# FRDM-TFC.net
KiCad netlist of a schematic drawn in Altium Designer
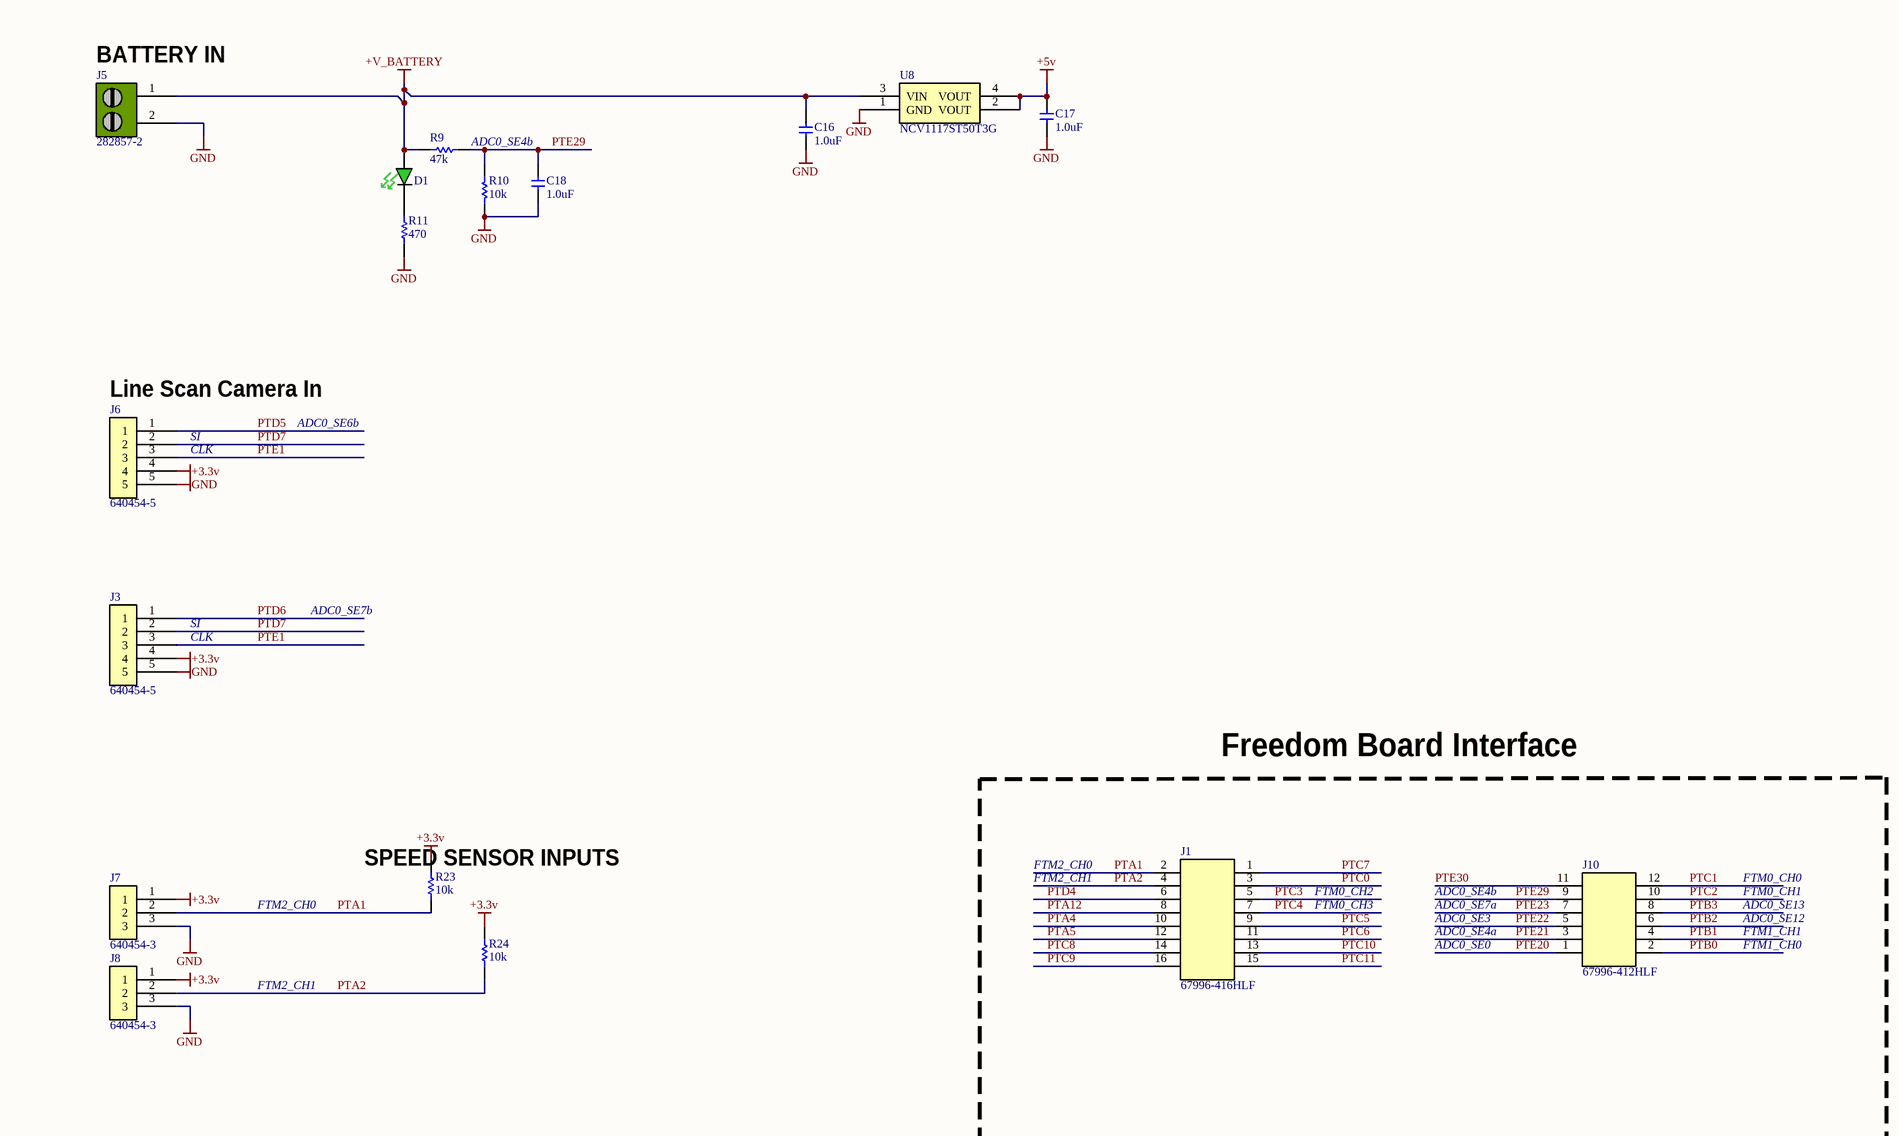
[diagram p0: FRDM-TFC.SchDoc, top left]
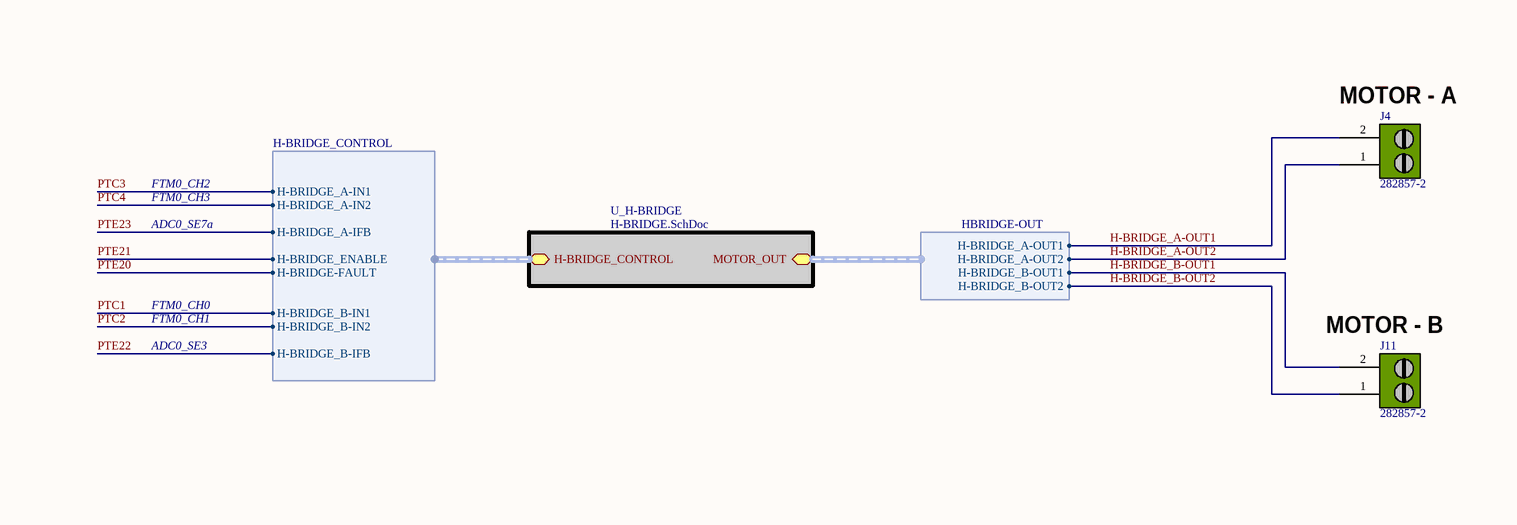
[diagram p1: FRDM-TFC.SchDoc, top right]
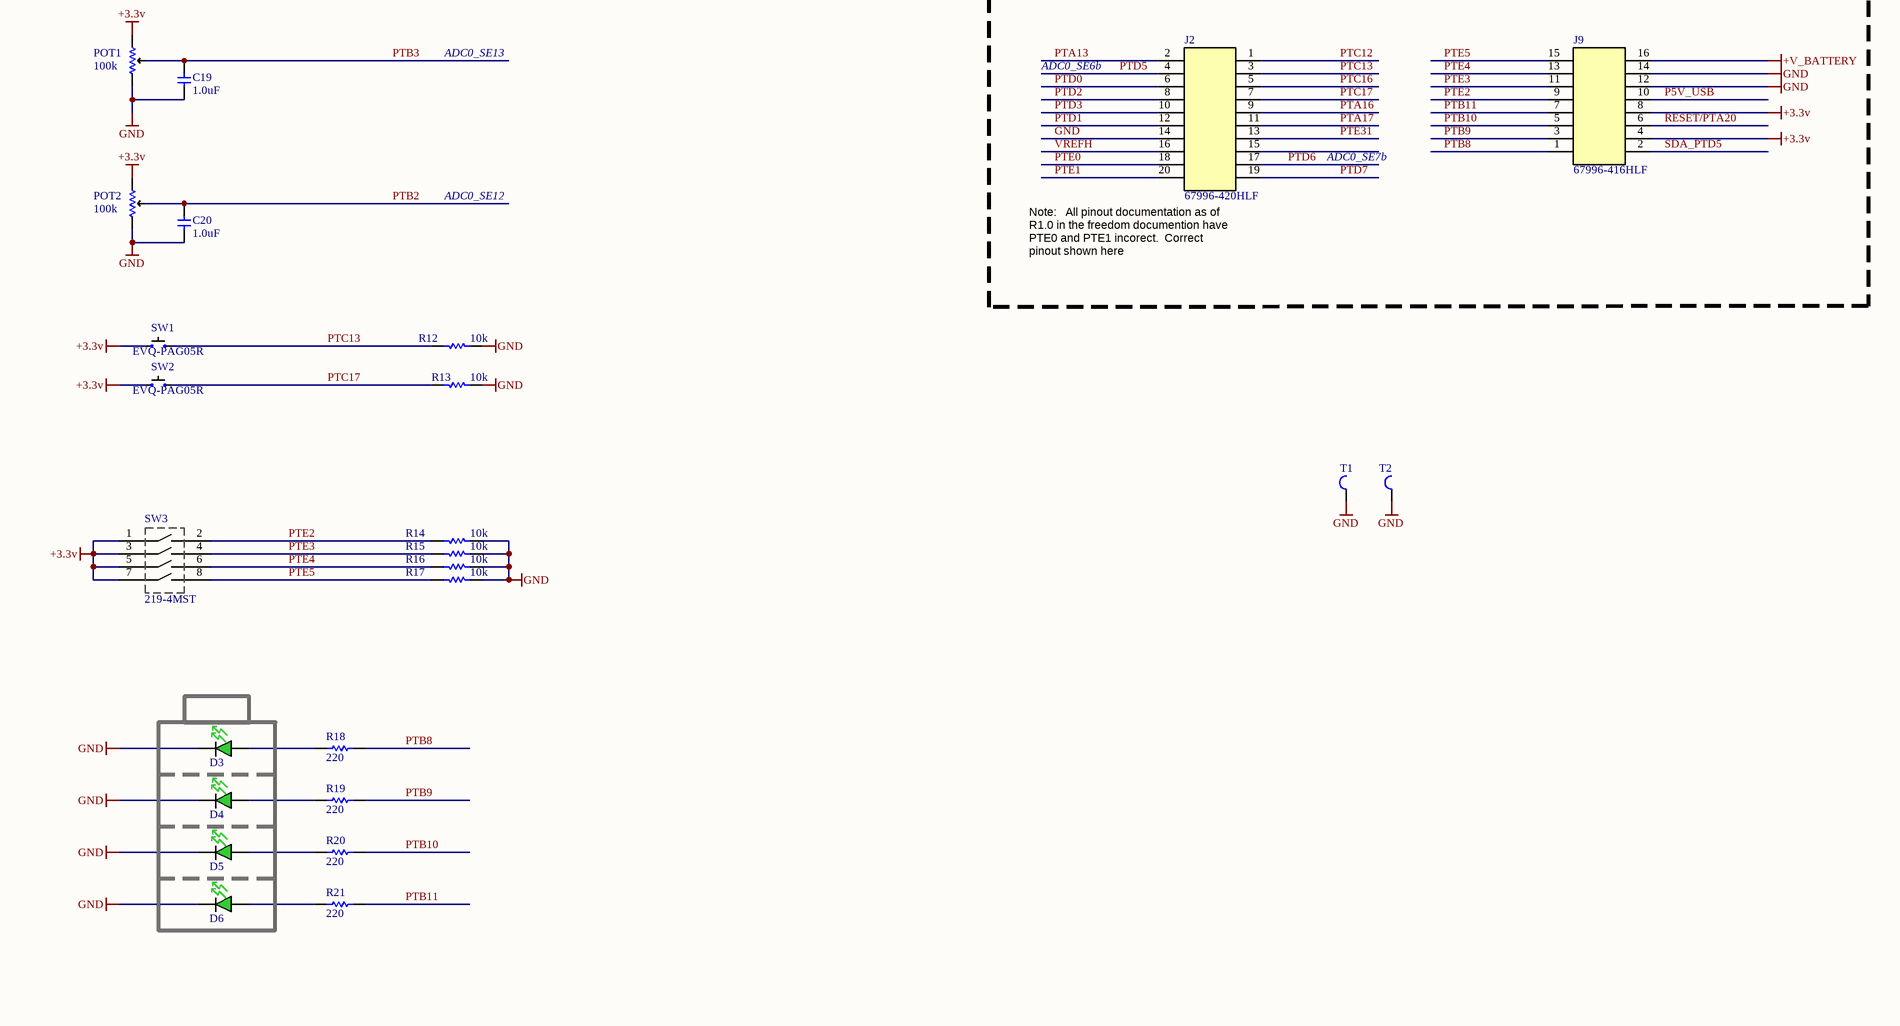
[diagram p2: FRDM-TFC.SchDoc, bottom left]
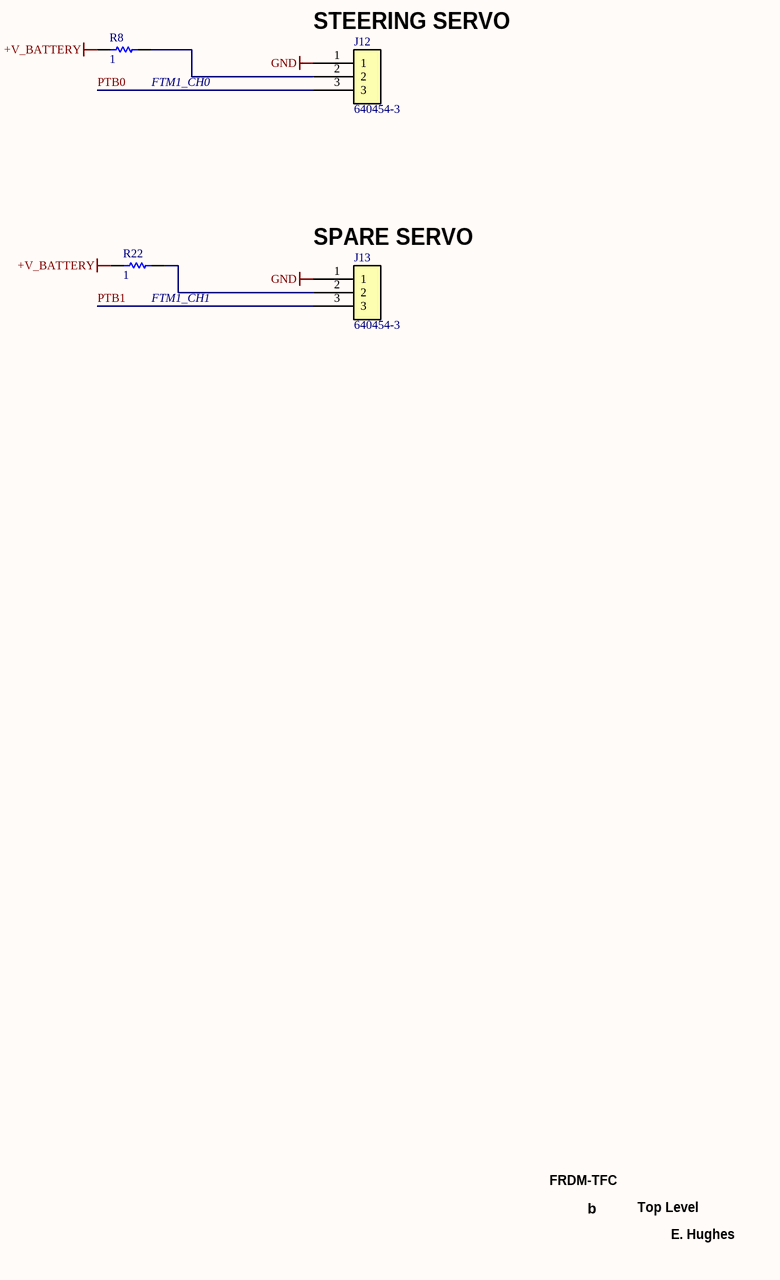
[diagram p3: FRDM-TFC.SchDoc, bottom right]

(export (version "E")
  (design (tool "Eeschema 10.0.6"))
  (components
    (comp (ref "C16")
      (value "1.0uF")
      (footprint "C0805")
      (description "CAP CER 1.0UF 50V X5R 0805")
      (fields
        (field (name "MANUFACTURER") "Taiyo Yuden")
        (field (name "MANUFACTURER PART NUMBER") "UMK212BJ105KG-T")
      )
      (libsource (lib "eCapacitors") (part "UMK212BJ105KG-T"))
    )
    (comp (ref "C17")
      (value "1.0uF")
      (footprint "C0805")
      (description "CAP CER 1.0UF 50V X5R 0805")
      (fields
        (field (name "MANUFACTURER") "Taiyo Yuden")
        (field (name "MANUFACTURER PART NUMBER") "UMK212BJ105KG-T")
      )
      (libsource (lib "eCapacitors") (part "UMK212BJ105KG-T"))
    )
    (comp (ref "C18")
      (value "1.0uF")
      (footprint "C0805")
      (description "CAP CER 1.0UF 50V X5R 0805")
      (fields
        (field (name "MANUFACTURER") "Taiyo Yuden")
        (field (name "MANUFACTURER PART NUMBER") "UMK212BJ105KG-T")
      )
      (libsource (lib "eCapacitors") (part "UMK212BJ105KG-T"))
    )
    (comp (ref "C19")
      (value "1.0uF")
      (footprint "C0805")
      (description "CAP CER 1.0UF 50V X5R 0805")
      (fields
        (field (name "MANUFACTURER") "Taiyo Yuden")
        (field (name "MANUFACTURER PART NUMBER") "UMK212BJ105KG-T")
      )
      (libsource (lib "eCapacitors") (part "UMK212BJ105KG-T"))
    )
    (comp (ref "C20")
      (value "1.0uF")
      (footprint "C0805")
      (description "CAP CER 1.0UF 50V X5R 0805")
      (fields
        (field (name "MANUFACTURER") "Taiyo Yuden")
        (field (name "MANUFACTURER PART NUMBER") "UMK212BJ105KG-T")
      )
      (libsource (lib "eCapacitors") (part "UMK212BJ105KG-T"))
    )
    (comp (ref "D1")
      (value "~")
      (footprint "LED_0805 - GREEN")
      (description "LED 2X1.2MM 570NM GN WTR CLR SMD")
      (fields
        (field (name "MANUFACTURER") "Kingbright Corp")
        (field (name "MANUFACTURER PART NUMBER") "APT2012CGCK")
      )
      (libsource (lib "eDiode") (part "APT2012CGCK"))
    )
    (comp (ref "D3")
      (value "~")
      (footprint "LED_0805 - GREEN")
      (description "LED 2X1.2MM 570NM GN WTR CLR SMD")
      (fields
        (field (name "MANUFACTURER") "Kingbright Corp")
        (field (name "MANUFACTURER PART NUMBER") "APT2012CGCK")
      )
      (libsource (lib "eDiode") (part "APT2012CGCK"))
    )
    (comp (ref "D4")
      (value "~")
      (footprint "LED_0805 - GREEN")
      (description "LED 2X1.2MM 570NM GN WTR CLR SMD")
      (fields
        (field (name "MANUFACTURER") "Kingbright Corp")
        (field (name "MANUFACTURER PART NUMBER") "APT2012CGCK")
      )
      (libsource (lib "eDiode") (part "APT2012CGCK"))
    )
    (comp (ref "D5")
      (value "~")
      (footprint "LED_0805 - GREEN")
      (description "LED 2X1.2MM 570NM GN WTR CLR SMD")
      (fields
        (field (name "MANUFACTURER") "Kingbright Corp")
        (field (name "MANUFACTURER PART NUMBER") "APT2012CGCK")
      )
      (libsource (lib "eDiode") (part "APT2012CGCK"))
    )
    (comp (ref "D6")
      (value "~")
      (footprint "LED_0805 - GREEN")
      (description "LED 2X1.2MM 570NM GN WTR CLR SMD")
      (fields
        (field (name "MANUFACTURER") "Kingbright Corp")
        (field (name "MANUFACTURER PART NUMBER") "APT2012CGCK")
      )
      (libsource (lib "eDiode") (part "APT2012CGCK"))
    )
    (comp (ref "J1")
      (value "67996-416HLF")
      (footprint "67996-416HLF")
      (description "CONN HEADER 16POS .100 STR TIN")
      (fields (field (name "MANUFACTURER") "FCI"))
      (libsource (lib "") (part "67996-416HLF_1"))
    )
    (comp (ref "J2")
      (value "67996-420HLF")
      (footprint "67996-420HLF")
      (description "CONN HEADER 20POS .100 STR TIN")
      (fields (field (name "MANUFACTURER") "FCI"))
      (libsource (lib "eConnector") (part "67996-420HLF"))
    )
    (comp (ref "J3")
      (value "640454-5")
      (footprint "640454-5")
      (description "CONN HEADER VERT 5POS .100 TIN")
      (fields (field (name "MANUFACTURER") "TE Connectivity"))
      (libsource (lib "eConnector") (part "640454-5"))
    )
    (comp (ref "J4")
      (value "282857-2")
      (footprint "282857-2")
      (description "TERM BLOCK 2POS SIDE ENT 5.08MM")
      (fields (field (name "MANUFACTURER") "TE Connectivity") (field (name "VOLTAGE") "300V"))
      (libsource (lib "eConnector") (part "282857-2"))
    )
    (comp (ref "J5")
      (value "282857-2")
      (footprint "282857-2")
      (description "TERM BLOCK 2POS SIDE ENT 5.08MM")
      (fields (field (name "MANUFACTURER") "TE Connectivity") (field (name "VOLTAGE") "300V"))
      (libsource (lib "") (part "282857-2_1"))
    )
    (comp (ref "J6")
      (value "640454-5")
      (footprint "640454-5")
      (description "CONN HEADER VERT 5POS .100 TIN")
      (fields (field (name "MANUFACTURER") "TE Connectivity"))
      (libsource (lib "eConnector") (part "640454-5"))
    )
    (comp (ref "J7")
      (value "640454-3")
      (footprint "640454-3")
      (description "CONN HEADER VERT 3POS .100 TIN")
      (fields (field (name "MANUFACTURER") "TE Connectivity"))
      (libsource (lib "eConnector") (part "640454-3"))
    )
    (comp (ref "J8")
      (value "640454-3")
      (footprint "640454-3")
      (description "CONN HEADER VERT 3POS .100 TIN")
      (fields (field (name "MANUFACTURER") "TE Connectivity"))
      (libsource (lib "eConnector") (part "640454-3"))
    )
    (comp (ref "J9")
      (value "67996-416HLF")
      (footprint "67996-416HLF")
      (description "CONN HEADER 16POS .100 STR TIN")
      (fields (field (name "MANUFACTURER") "FCI"))
      (libsource (lib "eConnector") (part "67996-416HLF"))
    )
    (comp (ref "J10")
      (value "67996-412HLF")
      (footprint "67996-412HLF")
      (description "CONN HEADER 12POS .100 STR TIN")
      (fields (field (name "MANUFACTURER") "FCI"))
      (libsource (lib "eConnector") (part "67996-412HLF"))
    )
    (comp (ref "J11")
      (value "282857-2")
      (footprint "282857-2")
      (description "TERM BLOCK 2POS SIDE ENT 5.08MM")
      (fields (field (name "MANUFACTURER") "TE Connectivity") (field (name "VOLTAGE") "300V"))
      (libsource (lib "eConnector") (part "282857-2"))
    )
    (comp (ref "J12")
      (value "640454-3")
      (footprint "640454-3")
      (description "CONN HEADER VERT 3POS .100 TIN")
      (fields (field (name "MANUFACTURER") "TE Connectivity"))
      (libsource (lib "") (part "640454-3_1"))
    )
    (comp (ref "J13")
      (value "640454-3")
      (footprint "640454-3")
      (description "CONN HEADER VERT 3POS .100 TIN")
      (fields (field (name "MANUFACTURER") "TE Connectivity"))
      (libsource (lib "") (part "640454-3_1"))
    )
    (comp (ref "POT1")
      (value "100k")
      (footprint "3386P")
      (description "TRIMMER 100K OHM 0.5W TH")
      (fields (field (name "MANUFACTURER") "Bourns Inc.") (field (name "TOLERANCE") "±10%"))
      (libsource (lib "ePotentiometer") (part "3386P-1-104TLF"))
    )
    (comp (ref "POT2")
      (value "100k")
      (footprint "3386P")
      (description "TRIMMER 100K OHM 0.5W TH")
      (fields (field (name "MANUFACTURER") "Bourns Inc.") (field (name "TOLERANCE") "±10%"))
      (libsource (lib "ePotentiometer") (part "3386P-1-104TLF"))
    )
    (comp (ref "R8")
      (value "1")
      (footprint "R2512")
      (description "RES 1.0 OHM 1W 5% 2512 SMD")
      (fields
        (field (name "MANUFACTURER") "Panasonic Electronic Components")
        (field (name "MANUFACTURER PART NUMBER") "ERJ-1TYJ1R0U")
      )
      (libsource (lib "eResistors") (part "ERJ-1TYJ1R0U"))
    )
    (comp (ref "R9")
      (value "47k")
      (footprint "R0603")
      (description "RES 47.0K OHM 1/10W 1% 0603 SMD")
      (fields
        (field (name "MANUFACTURER") "Panasonic - ECG")
        (field (name "MANUFACTURER PART NUMBER") "ERJ-3EKF4702V")
      )
      (libsource (lib "eResistors") (part "ERJ-3EKF4702V"))
    )
    (comp (ref "R10")
      (value "10k")
      (footprint "R0603")
      (description "RES 10.0K OHM 1/10W 1% 0603 SMD")
      (fields
        (field (name "MANUFACTURER") "Panasonic - ECG")
        (field (name "MANUFACTURER PART NUMBER") "ERJ-3EKF1002V")
      )
      (libsource (lib "eResistors") (part "ERJ-3EKF1002V"))
    )
    (comp (ref "R11")
      (value "470")
      (footprint "R0603")
      (description "RES 470 OHM 1/10W 1% 0603 SMD")
      (fields
        (field (name "MANUFACTURER") "Panasonic - ECG")
        (field (name "MANUFACTURER PART NUMBER") "ERJ-3EKF4700V")
      )
      (libsource (lib "eResistors") (part "ERJ-3EKF4700V"))
    )
    (comp (ref "R12")
      (value "10k")
      (footprint "R0603")
      (description "RES 10.0K OHM 1/10W 1% 0603 SMD")
      (fields
        (field (name "MANUFACTURER") "Panasonic - ECG")
        (field (name "MANUFACTURER PART NUMBER") "ERJ-3EKF1002V")
      )
      (libsource (lib "eResistors") (part "ERJ-3EKF1002V"))
    )
    (comp (ref "R13")
      (value "10k")
      (footprint "R0603")
      (description "RES 10.0K OHM 1/10W 1% 0603 SMD")
      (fields
        (field (name "MANUFACTURER") "Panasonic - ECG")
        (field (name "MANUFACTURER PART NUMBER") "ERJ-3EKF1002V")
      )
      (libsource (lib "eResistors") (part "ERJ-3EKF1002V"))
    )
    (comp (ref "R14")
      (value "10k")
      (footprint "R0603")
      (description "RES 10.0K OHM 1/10W 1% 0603 SMD")
      (fields
        (field (name "MANUFACTURER") "Panasonic - ECG")
        (field (name "MANUFACTURER PART NUMBER") "ERJ-3EKF1002V")
      )
      (libsource (lib "eResistors") (part "ERJ-3EKF1002V"))
    )
    (comp (ref "R15")
      (value "10k")
      (footprint "R0603")
      (description "RES 10.0K OHM 1/10W 1% 0603 SMD")
      (fields
        (field (name "MANUFACTURER") "Panasonic - ECG")
        (field (name "MANUFACTURER PART NUMBER") "ERJ-3EKF1002V")
      )
      (libsource (lib "eResistors") (part "ERJ-3EKF1002V"))
    )
    (comp (ref "R16")
      (value "10k")
      (footprint "R0603")
      (description "RES 10.0K OHM 1/10W 1% 0603 SMD")
      (fields
        (field (name "MANUFACTURER") "Panasonic - ECG")
        (field (name "MANUFACTURER PART NUMBER") "ERJ-3EKF1002V")
      )
      (libsource (lib "eResistors") (part "ERJ-3EKF1002V"))
    )
    (comp (ref "R17")
      (value "10k")
      (footprint "R0603")
      (description "RES 10.0K OHM 1/10W 1% 0603 SMD")
      (fields
        (field (name "MANUFACTURER") "Panasonic - ECG")
        (field (name "MANUFACTURER PART NUMBER") "ERJ-3EKF1002V")
      )
      (libsource (lib "eResistors") (part "ERJ-3EKF1002V"))
    )
    (comp (ref "R18")
      (value "220")
      (footprint "R0603")
      (description "RES 220 OHM 1/10W 1% 0603 SMD")
      (fields
        (field (name "MANUFACTURER") "Panasonic - ECG")
        (field (name "MANUFACTURER PART NUMBER") "ERJ-3EKF2200V")
      )
      (libsource (lib "eResistors") (part "ERJ-3EKF2200V"))
    )
    (comp (ref "R19")
      (value "220")
      (footprint "R0603")
      (description "RES 220 OHM 1/10W 1% 0603 SMD")
      (fields
        (field (name "MANUFACTURER") "Panasonic - ECG")
        (field (name "MANUFACTURER PART NUMBER") "ERJ-3EKF2200V")
      )
      (libsource (lib "eResistors") (part "ERJ-3EKF2200V"))
    )
    (comp (ref "R20")
      (value "220")
      (footprint "R0603")
      (description "RES 220 OHM 1/10W 1% 0603 SMD")
      (fields
        (field (name "MANUFACTURER") "Panasonic - ECG")
        (field (name "MANUFACTURER PART NUMBER") "ERJ-3EKF2200V")
      )
      (libsource (lib "eResistors") (part "ERJ-3EKF2200V"))
    )
    (comp (ref "R21")
      (value "220")
      (footprint "R0603")
      (description "RES 220 OHM 1/10W 1% 0603 SMD")
      (fields
        (field (name "MANUFACTURER") "Panasonic - ECG")
        (field (name "MANUFACTURER PART NUMBER") "ERJ-3EKF2200V")
      )
      (libsource (lib "eResistors") (part "ERJ-3EKF2200V"))
    )
    (comp (ref "R22")
      (value "1")
      (footprint "R2512")
      (description "RES 1.0 OHM 1W 5% 2512 SMD")
      (fields
        (field (name "MANUFACTURER") "Panasonic Electronic Components")
        (field (name "MANUFACTURER PART NUMBER") "ERJ-1TYJ1R0U")
      )
      (libsource (lib "eResistors") (part "ERJ-1TYJ1R0U"))
    )
    (comp (ref "R23")
      (value "10k")
      (footprint "R0603")
      (description "RES 10.0K OHM 1/10W 1% 0603 SMD")
      (fields
        (field (name "MANUFACTURER") "Panasonic - ECG")
        (field (name "TOLERANCE") "±1%")
        (field (name "SOURCE") "Digikey")
      )
      (libsource (lib "eRCL") (part "ERJ-3EKF1002V"))
    )
    (comp (ref "R24")
      (value "10k")
      (footprint "R0603")
      (description "RES 10.0K OHM 1/10W 1% 0603 SMD")
      (fields
        (field (name "MANUFACTURER") "Panasonic - ECG")
        (field (name "TOLERANCE") "±1%")
        (field (name "SOURCE") "Digikey")
      )
      (libsource (lib "eRCL") (part "ERJ-3EKF1002V"))
    )
    (comp (ref "SW1")
      (value "EVQ-PAG05R")
      (footprint "EVQ-PAG05R")
      (description "SWITCH LT 6MM 260GF 5MM HEIGHT")
      (fields (field (name "MANUFACTURER") "Panasonic - ECG") (field (name "SOURCE") "Digikey"))
      (libsource (lib "eElectroMechanical") (part "EVQ-PAG05R"))
    )
    (comp (ref "SW2")
      (value "EVQ-PAG05R")
      (footprint "EVQ-PAG05R")
      (description "SWITCH LT 6MM 260GF 5MM HEIGHT")
      (fields (field (name "MANUFACTURER") "Panasonic - ECG") (field (name "SOURCE") "Digikey"))
      (libsource (lib "eElectroMechanical") (part "EVQ-PAG05R"))
    )
    (comp (ref "SW3")
      (value "219-4MST")
      (footprint "219-4MST")
      (description "SWITCH TAPE SEAL 4 POS SMD")
      (fields (field (name "MANUFACTURER") "CTS Electrocomponents"))
      (libsource (lib "eElectroMechanical") (part "219-4MST"))
    )
    (comp (ref "T1")
      (value "PC TEST POINT MINIATURE SMT")
      (footprint "SMT_TEST_5015")
      (fields
        (field (name "MANUFACTURER") "Keystone Electronics")
        (field (name "MANUFACTURER PART NUMBER") "5015")
      )
      (libsource (lib "eConnector") (part "5015"))
    )
    (comp (ref "T2")
      (value "PC TEST POINT MINIATURE SMT")
      (footprint "SMT_TEST_5015")
      (fields
        (field (name "MANUFACTURER") "Keystone Electronics")
        (field (name "MANUFACTURER PART NUMBER") "5015")
      )
      (libsource (lib "eConnector") (part "5015"))
    )
    (comp (ref "U8")
      (value "NCV1117ST50T3G")
      (footprint "SOT223")
      (description "Low Dropout (LDO) Regulators ANA 800mA LDO")
      (fields (field (name "MANUFACTURER") "ON Semiconductor"))
      (libsource (lib "eIC") (part "NCV1117ST50T3G"))
    )
  )
  (nets
    (net (code "3") (name "+3.3v") (class "Default")
      (node (ref "J3") (pin "4") (pinfunction "4_4") (pintype "passive"))
      (node (ref "J6") (pin "4") (pinfunction "4_4") (pintype "passive"))
      (node (ref "J7") (pin "1") (pinfunction "1_1") (pintype "passive"))
      (node (ref "J8") (pin "1") (pinfunction "1_1") (pintype "passive"))
      (node (ref "J9") (pin "4") (pinfunction "4_4") (pintype "passive"))
      (node (ref "J9") (pin "8") (pinfunction "8_8") (pintype "passive"))
      (node (ref "POT1") (pin "1") (pinfunction "1_1") (pintype "passive"))
      (node (ref "POT2") (pin "1") (pinfunction "1_1") (pintype "passive"))
      (node (ref "R23") (pin "2") (pinfunction "2_2") (pintype "passive"))
      (node (ref "R24") (pin "2") (pinfunction "2_2") (pintype "passive"))
      (node (ref "SW1") (pin "A") (pinfunction "A_A") (pintype "passive"))
      (node (ref "SW2") (pin "A") (pinfunction "A_A") (pintype "passive"))
      (node (ref "SW3") (pin "1") (pinfunction "A1_1") (pintype "passive"))
      (node (ref "SW3") (pin "3") (pinfunction "A2_3") (pintype "passive"))
      (node (ref "SW3") (pin "5") (pinfunction "A3_5") (pintype "passive"))
      (node (ref "SW3") (pin "7") (pinfunction "A4_7") (pintype "passive"))
    )
    (net (code "4") (name "+5v") (class "Default")
      (node (ref "C17") (pin "1") (pinfunction "1_1") (pintype "passive"))
      (node (ref "U8") (pin "2") (pinfunction "VOUT_2") (pintype "passive"))
      (node (ref "U8") (pin "4") (pinfunction "VOUT_4") (pintype "passive"))
    )
    (net (code "5") (name "+V_BATTERY") (class "Default")
      (node (ref "C16") (pin "1") (pinfunction "1_1") (pintype "passive"))
      (node (ref "D1") (pin "A") (pinfunction "A_A") (pintype "passive"))
      (node (ref "J5") (pin "1") (pinfunction "1_1") (pintype "passive"))
      (node (ref "J9") (pin "16") (pinfunction "16_16") (pintype "passive"))
      (node (ref "R22") (pin "1") (pinfunction "1_1") (pintype "passive"))
      (node (ref "R8") (pin "1") (pinfunction "1_1") (pintype "passive"))
      (node (ref "R9") (pin "1") (pinfunction "1_1") (pintype "passive"))
      (node (ref "U8") (pin "3") (pinfunction "VIN_3") (pintype "passive"))
    )
    (net (code "6") (name "/H-BRIDGE_A-OUT1") (class "Default")
      (node (ref "J4") (pin "2") (pinfunction "2_2") (pintype "passive"))
    )
    (net (code "7") (name "/H-BRIDGE_A-OUT2") (class "Default")
      (node (ref "J4") (pin "1") (pinfunction "1_1") (pintype "passive"))
    )
    (net (code "8") (name "/H-BRIDGE_B-OUT1") (class "Default")
      (node (ref "J11") (pin "2") (pinfunction "2_2") (pintype "passive"))
    )
    (net (code "9") (name "/H-BRIDGE_B-OUT2") (class "Default")
      (node (ref "J11") (pin "1") (pinfunction "1_1") (pintype "passive"))
    )
    (net (code "10") (name "/P5V_USB") (class "Default")
      (node (ref "J9") (pin "10") (pinfunction "10_10") (pintype "passive"))
    )
    (net (code "11") (name "/PTA1") (class "Default")
      (node (ref "J1") (pin "2") (pinfunction "2_2") (pintype "passive"))
      (node (ref "J7") (pin "2") (pinfunction "2_2") (pintype "passive"))
      (node (ref "R23") (pin "1") (pinfunction "1_1") (pintype "passive"))
    )
    (net (code "12") (name "/PTA2") (class "Default")
      (node (ref "J1") (pin "4") (pinfunction "4_4") (pintype "passive"))
      (node (ref "J8") (pin "2") (pinfunction "2_2") (pintype "passive"))
      (node (ref "R24") (pin "1") (pinfunction "1_1") (pintype "passive"))
    )
    (net (code "13") (name "/PTA4") (class "Default")
      (node (ref "J1") (pin "10") (pinfunction "10_10") (pintype "passive"))
    )
    (net (code "14") (name "/PTA5") (class "Default")
      (node (ref "J1") (pin "12") (pinfunction "12_12") (pintype "passive"))
    )
    (net (code "15") (name "/PTA12") (class "Default")
      (node (ref "J1") (pin "8") (pinfunction "8_8") (pintype "passive"))
    )
    (net (code "16") (name "/PTA13") (class "Default")
      (node (ref "J2") (pin "2") (pinfunction "2_2") (pintype "passive"))
    )
    (net (code "17") (name "/PTA16") (class "Default")
      (node (ref "J2") (pin "9") (pinfunction "9_9") (pintype "passive"))
    )
    (net (code "18") (name "/PTA17") (class "Default")
      (node (ref "J2") (pin "11") (pinfunction "11_11") (pintype "passive"))
    )
    (net (code "19") (name "/PTB0") (class "Default")
      (node (ref "J10") (pin "2") (pinfunction "2_2") (pintype "passive"))
      (node (ref "J12") (pin "3") (pinfunction "3_3") (pintype "passive"))
    )
    (net (code "20") (name "/PTB1") (class "Default")
      (node (ref "J10") (pin "4") (pinfunction "4_4") (pintype "passive"))
      (node (ref "J13") (pin "3") (pinfunction "3_3") (pintype "passive"))
    )
    (net (code "21") (name "/PTB2") (class "Default")
      (node (ref "C20") (pin "2") (pinfunction "2_2") (pintype "passive"))
      (node (ref "J10") (pin "6") (pinfunction "6_6") (pintype "passive"))
      (node (ref "POT2") (pin "2") (pinfunction "2_2") (pintype "passive"))
    )
    (net (code "22") (name "/PTB3") (class "Default")
      (node (ref "C19") (pin "2") (pinfunction "2_2") (pintype "passive"))
      (node (ref "J10") (pin "8") (pinfunction "8_8") (pintype "passive"))
      (node (ref "POT1") (pin "2") (pinfunction "2_2") (pintype "passive"))
    )
    (net (code "23") (name "/PTB8") (class "Default")
      (node (ref "J9") (pin "1") (pinfunction "1_1") (pintype "passive"))
      (node (ref "R18") (pin "1") (pinfunction "1_1") (pintype "passive"))
    )
    (net (code "24") (name "/PTB9") (class "Default")
      (node (ref "J9") (pin "3") (pinfunction "3_3") (pintype "passive"))
      (node (ref "R19") (pin "1") (pinfunction "1_1") (pintype "passive"))
    )
    (net (code "25") (name "/PTB10") (class "Default")
      (node (ref "J9") (pin "5") (pinfunction "5_5") (pintype "passive"))
      (node (ref "R20") (pin "1") (pinfunction "1_1") (pintype "passive"))
    )
    (net (code "26") (name "/PTB11") (class "Default")
      (node (ref "J9") (pin "7") (pinfunction "7_7") (pintype "passive"))
      (node (ref "R21") (pin "1") (pinfunction "1_1") (pintype "passive"))
    )
    (net (code "27") (name "/PTC0") (class "Default")
      (node (ref "J1") (pin "3") (pinfunction "3_3") (pintype "passive"))
    )
    (net (code "28") (name "/PTC1") (class "Default")
      (node (ref "J10") (pin "12") (pinfunction "12_12") (pintype "passive"))
    )
    (net (code "29") (name "/PTC2") (class "Default")
      (node (ref "J10") (pin "10") (pinfunction "10_10") (pintype "passive"))
    )
    (net (code "30") (name "/PTC3") (class "Default")
      (node (ref "J1") (pin "5") (pinfunction "5_5") (pintype "passive"))
    )
    (net (code "31") (name "/PTC4") (class "Default")
      (node (ref "J1") (pin "7") (pinfunction "7_7") (pintype "passive"))
    )
    (net (code "32") (name "/PTC5") (class "Default")
      (node (ref "J1") (pin "9") (pinfunction "9_9") (pintype "passive"))
    )
    (net (code "33") (name "/PTC6") (class "Default")
      (node (ref "J1") (pin "11") (pinfunction "11_11") (pintype "passive"))
    )
    (net (code "34") (name "/PTC7") (class "Default")
      (node (ref "J1") (pin "1") (pinfunction "1_1") (pintype "passive"))
    )
    (net (code "35") (name "/PTC8") (class "Default")
      (node (ref "J1") (pin "14") (pinfunction "14_14") (pintype "passive"))
    )
    (net (code "36") (name "/PTC9") (class "Default")
      (node (ref "J1") (pin "16") (pinfunction "16_16") (pintype "passive"))
    )
    (net (code "37") (name "/PTC10") (class "Default")
      (node (ref "J1") (pin "13") (pinfunction "13_13") (pintype "passive"))
    )
    (net (code "38") (name "/PTC11") (class "Default")
      (node (ref "J1") (pin "15") (pinfunction "15_15") (pintype "passive"))
    )
    (net (code "39") (name "/PTC12") (class "Default")
      (node (ref "J2") (pin "1") (pinfunction "1_1") (pintype "passive"))
    )
    (net (code "40") (name "/PTC13") (class "Default")
      (node (ref "J2") (pin "3") (pinfunction "3_3") (pintype "passive"))
      (node (ref "R12") (pin "2") (pinfunction "2_2") (pintype "passive"))
      (node (ref "SW1") (pin "B") (pinfunction "B_B") (pintype "passive"))
    )
    (net (code "41") (name "/PTC16") (class "Default")
      (node (ref "J2") (pin "5") (pinfunction "5_5") (pintype "passive"))
    )
    (net (code "42") (name "/PTC17") (class "Default")
      (node (ref "J2") (pin "7") (pinfunction "7_7") (pintype "passive"))
      (node (ref "R13") (pin "2") (pinfunction "2_2") (pintype "passive"))
      (node (ref "SW2") (pin "B") (pinfunction "B_B") (pintype "passive"))
    )
    (net (code "43") (name "/PTD0") (class "Default")
      (node (ref "J2") (pin "6") (pinfunction "6_6") (pintype "passive"))
    )
    (net (code "44") (name "/PTD1") (class "Default")
      (node (ref "J2") (pin "12") (pinfunction "12_12") (pintype "passive"))
    )
    (net (code "45") (name "/PTD2") (class "Default")
      (node (ref "J2") (pin "8") (pinfunction "8_8") (pintype "passive"))
    )
    (net (code "46") (name "/PTD3") (class "Default")
      (node (ref "J2") (pin "10") (pinfunction "10_10") (pintype "passive"))
    )
    (net (code "47") (name "/PTD4") (class "Default")
      (node (ref "J1") (pin "6") (pinfunction "6_6") (pintype "passive"))
    )
    (net (code "48") (name "/PTD5") (class "Default")
      (node (ref "J2") (pin "4") (pinfunction "4_4") (pintype "passive"))
      (node (ref "J6") (pin "1") (pinfunction "1_1") (pintype "passive"))
    )
    (net (code "49") (name "/PTD6") (class "Default")
      (node (ref "J2") (pin "17") (pinfunction "17_17") (pintype "passive"))
      (node (ref "J3") (pin "1") (pinfunction "1_1") (pintype "passive"))
    )
    (net (code "50") (name "/PTD7") (class "Default")
      (node (ref "J2") (pin "19") (pinfunction "19_19") (pintype "passive"))
      (node (ref "J3") (pin "2") (pinfunction "2_2") (pintype "passive"))
      (node (ref "J6") (pin "2") (pinfunction "2_2") (pintype "passive"))
    )
    (net (code "51") (name "/PTE0") (class "Default")
      (node (ref "J2") (pin "18") (pinfunction "18_18") (pintype "passive"))
    )
    (net (code "52") (name "/PTE1") (class "Default")
      (node (ref "J2") (pin "20") (pinfunction "20_20") (pintype "passive"))
      (node (ref "J3") (pin "3") (pinfunction "3_3") (pintype "passive"))
      (node (ref "J6") (pin "3") (pinfunction "3_3") (pintype "passive"))
    )
    (net (code "53") (name "/PTE2") (class "Default")
      (node (ref "J9") (pin "9") (pinfunction "9_9") (pintype "passive"))
      (node (ref "R14") (pin "2") (pinfunction "2_2") (pintype "passive"))
      (node (ref "SW3") (pin "2") (pinfunction "B1_2") (pintype "passive"))
    )
    (net (code "54") (name "/PTE3") (class "Default")
      (node (ref "J9") (pin "11") (pinfunction "11_11") (pintype "passive"))
      (node (ref "R15") (pin "2") (pinfunction "2_2") (pintype "passive"))
      (node (ref "SW3") (pin "4") (pinfunction "B2_4") (pintype "passive"))
    )
    (net (code "55") (name "/PTE4") (class "Default")
      (node (ref "J9") (pin "13") (pinfunction "13_13") (pintype "passive"))
      (node (ref "R16") (pin "2") (pinfunction "2_2") (pintype "passive"))
      (node (ref "SW3") (pin "6") (pinfunction "B3_6") (pintype "passive"))
    )
    (net (code "56") (name "/PTE5") (class "Default")
      (node (ref "J9") (pin "15") (pinfunction "15_15") (pintype "passive"))
      (node (ref "R17") (pin "2") (pinfunction "2_2") (pintype "passive"))
      (node (ref "SW3") (pin "8") (pinfunction "B4_8") (pintype "passive"))
    )
    (net (code "57") (name "/PTE20") (class "Default")
      (node (ref "J10") (pin "1") (pinfunction "1_1") (pintype "passive"))
    )
    (net (code "58") (name "/PTE21") (class "Default")
      (node (ref "J10") (pin "3") (pinfunction "3_3") (pintype "passive"))
    )
    (net (code "59") (name "/PTE22") (class "Default")
      (node (ref "J10") (pin "5") (pinfunction "5_5") (pintype "passive"))
    )
    (net (code "60") (name "/PTE23") (class "Default")
      (node (ref "J10") (pin "7") (pinfunction "7_7") (pintype "passive"))
    )
    (net (code "61") (name "/PTE29") (class "Default")
      (node (ref "C18") (pin "2") (pinfunction "2_2") (pintype "passive"))
      (node (ref "J10") (pin "9") (pinfunction "9_9") (pintype "passive"))
      (node (ref "R10") (pin "1") (pinfunction "1_1") (pintype "passive"))
      (node (ref "R9") (pin "2") (pinfunction "2_2") (pintype "passive"))
    )
    (net (code "62") (name "/PTE30") (class "Default")
      (node (ref "J10") (pin "11") (pinfunction "11_11") (pintype "passive"))
    )
    (net (code "63") (name "/PTE31") (class "Default")
      (node (ref "J2") (pin "13") (pinfunction "13_13") (pintype "passive"))
    )
    (net (code "64") (name "/RESET{slash}PTA20") (class "Default")
      (node (ref "J9") (pin "6") (pinfunction "6_6") (pintype "passive"))
    )
    (net (code "65") (name "/SDA_PTD5") (class "Default")
      (node (ref "J9") (pin "2") (pinfunction "2_2") (pintype "passive"))
    )
    (net (code "66") (name "/VREFH") (class "Default")
      (node (ref "J2") (pin "16") (pinfunction "16_16") (pintype "passive"))
    )
    (net (code "69") (name "GND") (class "Default")
      (node (ref "C16") (pin "2") (pinfunction "2_2") (pintype "passive"))
      (node (ref "C17") (pin "2") (pinfunction "2_2") (pintype "passive"))
      (node (ref "C18") (pin "1") (pinfunction "1_1") (pintype "passive"))
      (node (ref "C19") (pin "1") (pinfunction "1_1") (pintype "passive"))
      (node (ref "C20") (pin "1") (pinfunction "1_1") (pintype "passive"))
      (node (ref "D3") (pin "C") (pinfunction "C_C") (pintype "passive"))
      (node (ref "D4") (pin "C") (pinfunction "C_C") (pintype "passive"))
      (node (ref "D5") (pin "C") (pinfunction "C_C") (pintype "passive"))
      (node (ref "D6") (pin "C") (pinfunction "C_C") (pintype "passive"))
      (node (ref "J12") (pin "1") (pinfunction "1_1") (pintype "passive"))
      (node (ref "J13") (pin "1") (pinfunction "1_1") (pintype "passive"))
      (node (ref "J2") (pin "14") (pinfunction "14_14") (pintype "passive"))
      (node (ref "J3") (pin "5") (pinfunction "5_5") (pintype "passive"))
      (node (ref "J5") (pin "2") (pinfunction "2_2") (pintype "passive"))
      (node (ref "J6") (pin "5") (pinfunction "5_5") (pintype "passive"))
      (node (ref "J7") (pin "3") (pinfunction "3_3") (pintype "passive"))
      (node (ref "J8") (pin "3") (pinfunction "3_3") (pintype "passive"))
      (node (ref "J9") (pin "12") (pinfunction "12_12") (pintype "passive"))
      (node (ref "J9") (pin "14") (pinfunction "14_14") (pintype "passive"))
      (node (ref "POT1") (pin "3") (pinfunction "3_3") (pintype "passive"))
      (node (ref "POT2") (pin "3") (pinfunction "3_3") (pintype "passive"))
      (node (ref "R10") (pin "2") (pinfunction "2_2") (pintype "passive"))
      (node (ref "R11") (pin "1") (pinfunction "1_1") (pintype "passive"))
      (node (ref "R12") (pin "1") (pinfunction "1_1") (pintype "passive"))
      (node (ref "R13") (pin "1") (pinfunction "1_1") (pintype "passive"))
      (node (ref "R14") (pin "1") (pinfunction "1_1") (pintype "passive"))
      (node (ref "R15") (pin "1") (pinfunction "1_1") (pintype "passive"))
      (node (ref "R16") (pin "1") (pinfunction "1_1") (pintype "passive"))
      (node (ref "R17") (pin "1") (pinfunction "1_1") (pintype "passive"))
      (node (ref "T1") (pin "1") (pinfunction "1_1") (pintype "passive"))
      (node (ref "T2") (pin "1") (pinfunction "1_1") (pintype "passive"))
      (node (ref "U8") (pin "1") (pinfunction "GND_1") (pintype "passive"))
    )
    (net (code "70") (name "Net-(D1-PadC)") (class "Default")
      (node (ref "D1") (pin "C") (pinfunction "C_C") (pintype "passive"))
      (node (ref "R11") (pin "2") (pinfunction "2_2") (pintype "passive"))
    )
    (net (code "71") (name "Net-(D3-PadA)") (class "Default")
      (node (ref "D3") (pin "A") (pinfunction "A_A") (pintype "passive"))
      (node (ref "R18") (pin "2") (pinfunction "2_2") (pintype "passive"))
    )
    (net (code "72") (name "Net-(D4-PadA)") (class "Default")
      (node (ref "D4") (pin "A") (pinfunction "A_A") (pintype "passive"))
      (node (ref "R19") (pin "2") (pinfunction "2_2") (pintype "passive"))
    )
    (net (code "73") (name "Net-(D5-PadA)") (class "Default")
      (node (ref "D5") (pin "A") (pinfunction "A_A") (pintype "passive"))
      (node (ref "R20") (pin "2") (pinfunction "2_2") (pintype "passive"))
    )
    (net (code "74") (name "Net-(D6-PadA)") (class "Default")
      (node (ref "D6") (pin "A") (pinfunction "A_A") (pintype "passive"))
      (node (ref "R21") (pin "2") (pinfunction "2_2") (pintype "passive"))
    )
    (net (code "75") (name "Net-(J12-Pad2)") (class "Default")
      (node (ref "J12") (pin "2") (pinfunction "2_2") (pintype "passive"))
      (node (ref "R8") (pin "2") (pinfunction "2_2") (pintype "passive"))
    )
    (net (code "76") (name "Net-(J13-Pad2)") (class "Default")
      (node (ref "J13") (pin "2") (pinfunction "2_2") (pintype "passive"))
      (node (ref "R22") (pin "2") (pinfunction "2_2") (pintype "passive"))
    )
    (net (code "77") (name "unconnected-(J2-Pad15)") (class "Default")
      (node (ref "J2") (pin "15") (pinfunction "15_15") (pintype "passive"))
    )
  )
)
